# SCH_Business-Card_2024-04-15_2.net
KiCad netlist of a schematic drawn in EasyEDA
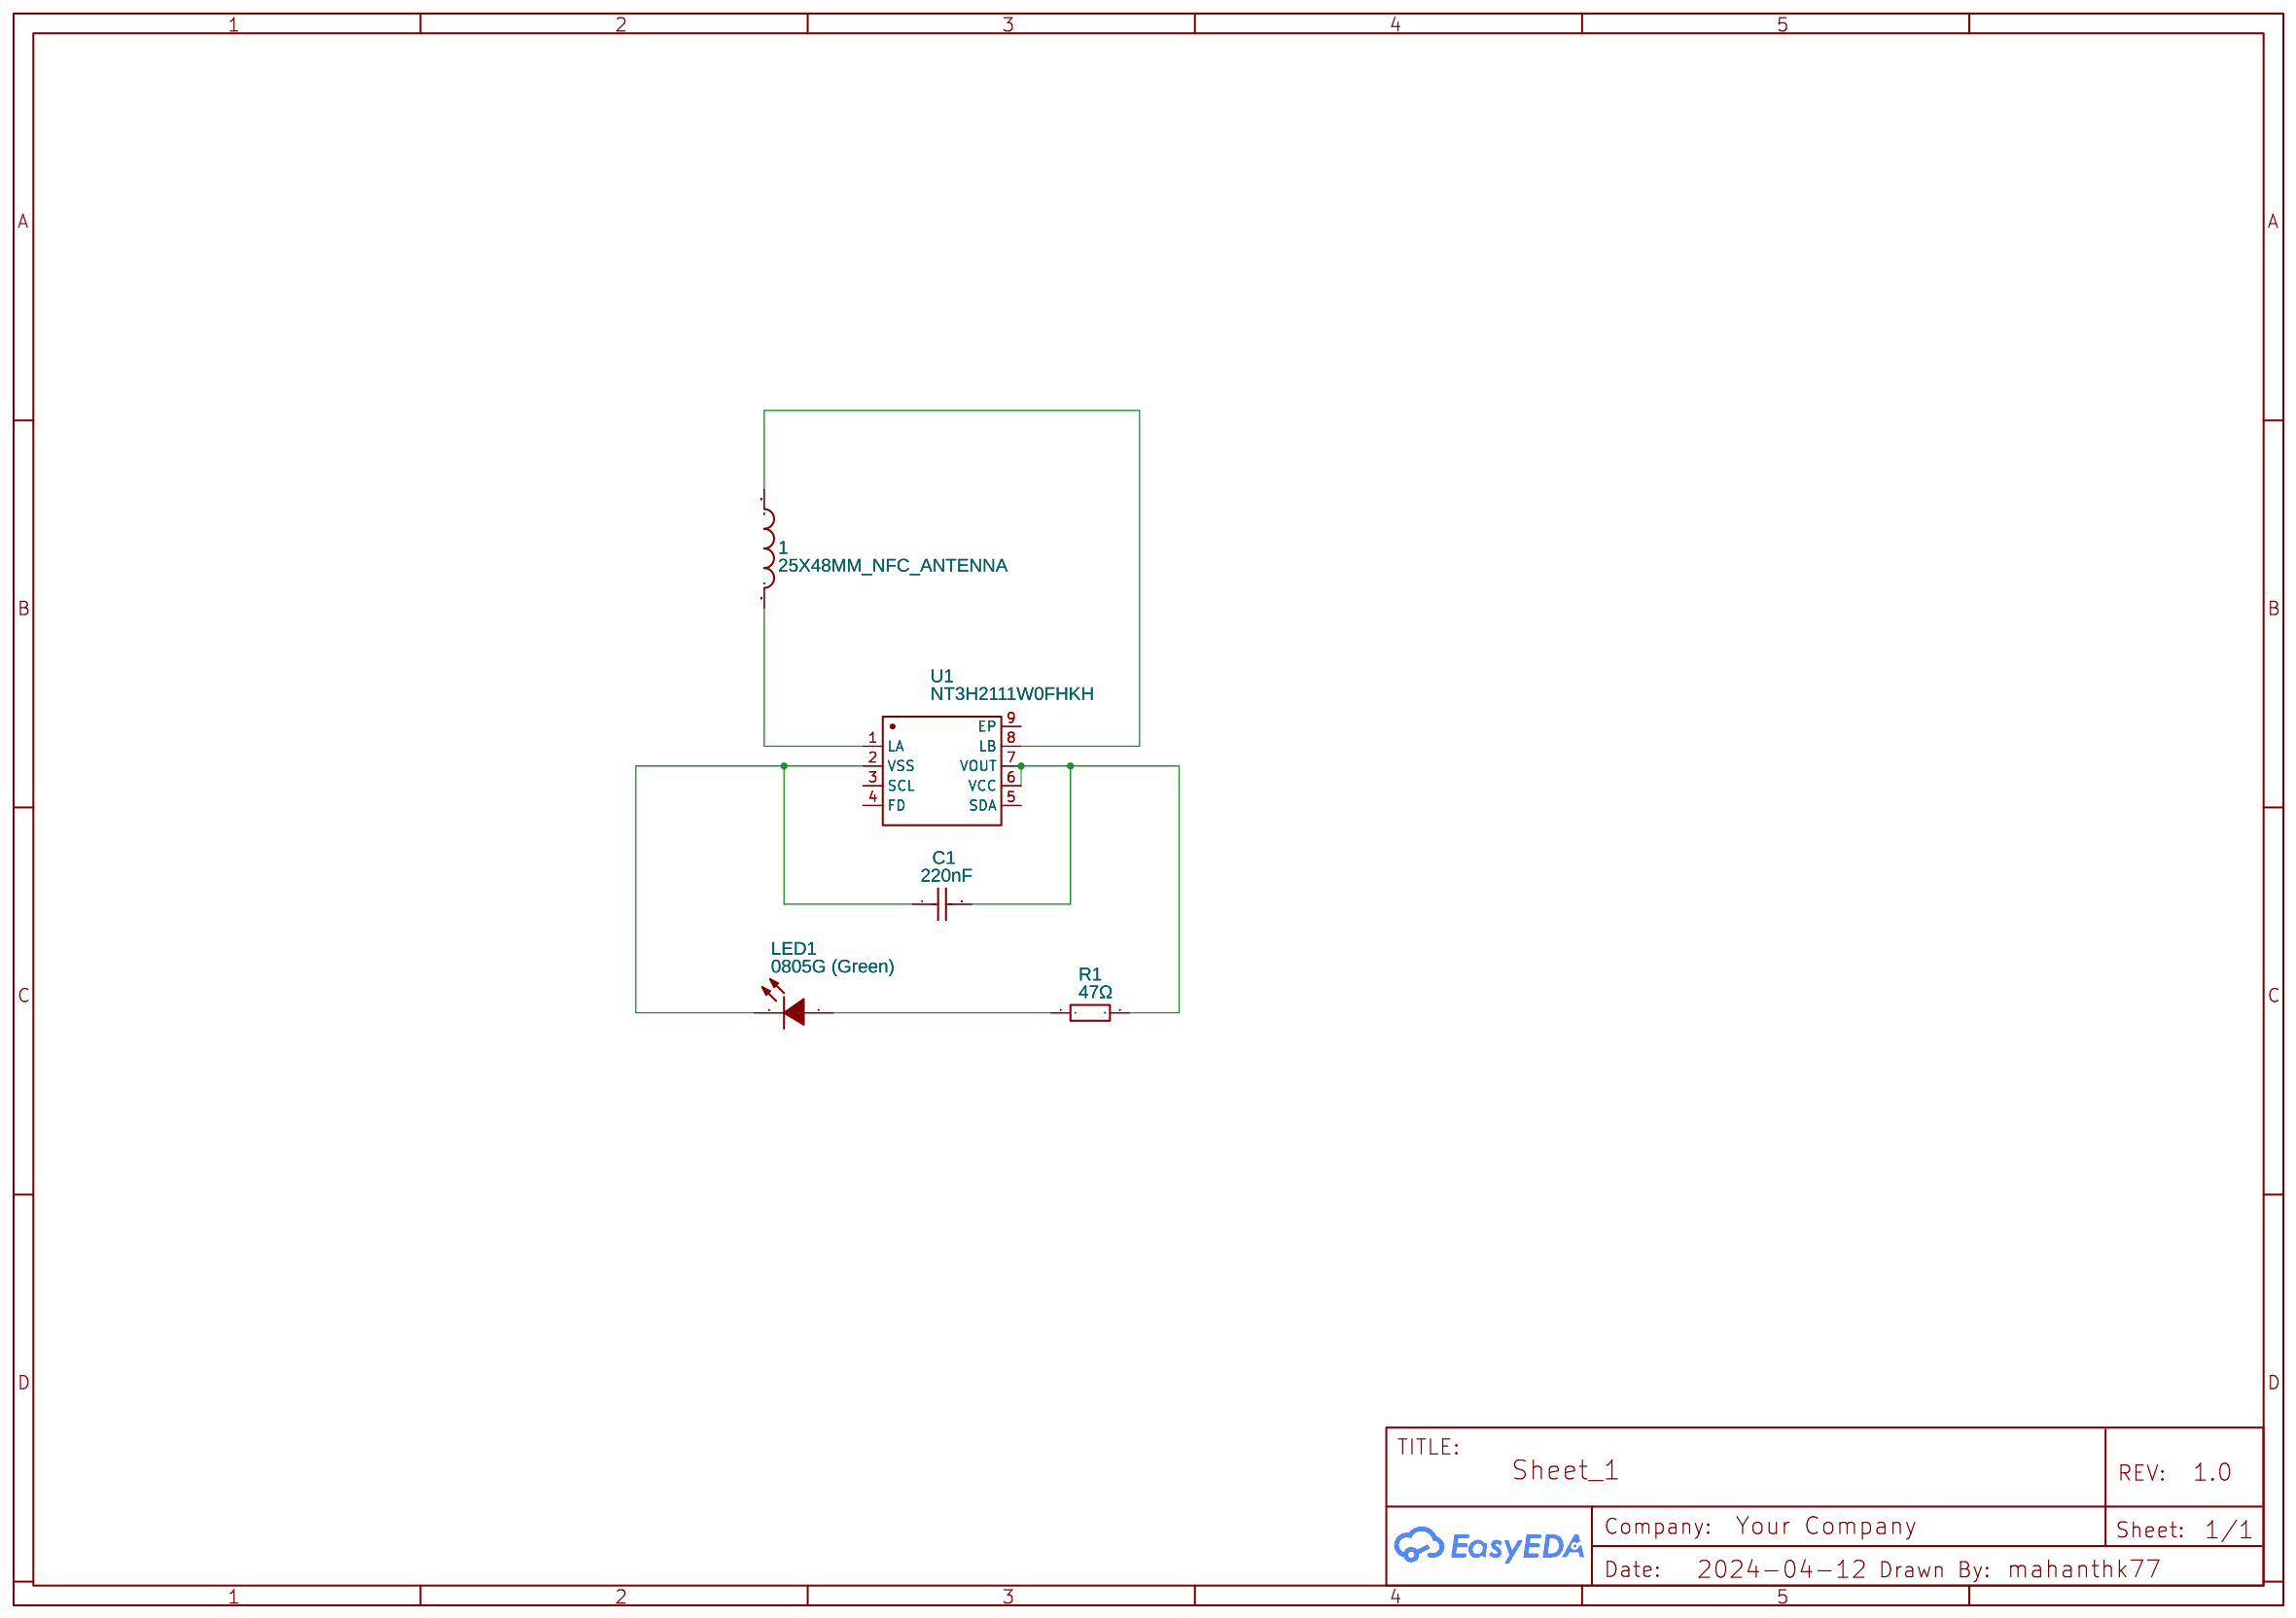
[diagram p0: schematic sheet]

(export (version "E")
  (design (tool "Eeschema 10.0.6"))
  (components
    (comp (ref "1") (value "25X48MM_NFC_ANTENNA") (libsource (lib "") (part "25X48MM_NFC_ANTENNA")))
    (comp (ref "C1")
      (value "220nF")
      (fields
        (field (name "Manufacturer Part") "CL10B224KA8NNNC")
        (field (name "Manufacturer") "SAMSUNG(三星)")
      )
      (libsource (lib "") (part "CL10B224KA8NNNC"))
    )
    (comp (ref "LED1")
      (value "0805G (Green)")
      (fields (field (name "Manufacturer Part") "KT-0805G") (field (name "Manufacturer") "KENTO"))
      (libsource (lib "") (part "0805G (Green)"))
    )
    (comp (ref "R1")
      (value "47Ω")
      (fields
        (field (name "Manufacturer Part") "0603WAF470JT5E")
        (field (name "Manufacturer") "UNI-ROYAL(厚声)")
      )
      (libsource (lib "") (part "0603WAF470JT5E"))
    )
    (comp (ref "U1")
      (value "NT3H2111W0FHKH")
      (fields (field (name "Manufacturer") "NXP(恩智浦)"))
      (libsource (lib "") (part "NT3H2111W0FHKH"))
    )
  )
  (nets
    (net (code "1") (name "Net-(LED1-A)") (class "Default")
      (node (ref "LED1") (pin "1") (pinfunction "A_1") (pintype "unspecified"))
      (node (ref "R1") (pin "1") (pinfunction "1_1") (pintype "input"))
    )
    (net (code "2") (name "Net-(LED1-K)") (class "Default")
      (node (ref "C1") (pin "1") (pinfunction "1_1") (pintype "input"))
      (node (ref "LED1") (pin "2") (pinfunction "K_2") (pintype "unspecified"))
      (node (ref "U1") (pin "2") (pinfunction "VSS_2") (pintype "unspecified"))
    )
    (net (code "3") (name "Net-(U1-LA)") (class "Default")
      (node (ref "1") (pin "P$2") (pinfunction "P$2_P$2") (pintype "bidirectional"))
      (node (ref "U1") (pin "1") (pinfunction "LA_1") (pintype "unspecified"))
    )
    (net (code "4") (name "Net-(U1-LB)") (class "Default")
      (node (ref "1") (pin "P$1") (pinfunction "P$1_P$1") (pintype "bidirectional"))
      (node (ref "U1") (pin "8") (pinfunction "LB_8") (pintype "unspecified"))
    )
    (net (code "5") (name "Net-(U1-VCC)") (class "Default")
      (node (ref "C1") (pin "2") (pinfunction "2_2") (pintype "input"))
      (node (ref "R1") (pin "2") (pinfunction "2_2") (pintype "input"))
      (node (ref "U1") (pin "6") (pinfunction "VCC_6") (pintype "unspecified"))
      (node (ref "U1") (pin "7") (pinfunction "VOUT_7") (pintype "unspecified"))
    )
    (net (code "6") (name "unconnected-(U1-EP-Pad9)") (class "Default")
      (node (ref "U1") (pin "9") (pinfunction "EP_9") (pintype "unspecified"))
    )
    (net (code "7") (name "unconnected-(U1-FD-Pad4)") (class "Default")
      (node (ref "U1") (pin "4") (pinfunction "FD_4") (pintype "unspecified"))
    )
    (net (code "8") (name "unconnected-(U1-SCL-Pad3)") (class "Default")
      (node (ref "U1") (pin "3") (pinfunction "SCL_3") (pintype "unspecified"))
    )
    (net (code "9") (name "unconnected-(U1-SDA-Pad5)") (class "Default")
      (node (ref "U1") (pin "5") (pinfunction "SDA_5") (pintype "unspecified"))
    )
  )
)
